# Dash_LEDs_r2.net
KiCad netlist of a schematic drawn in EAGLE
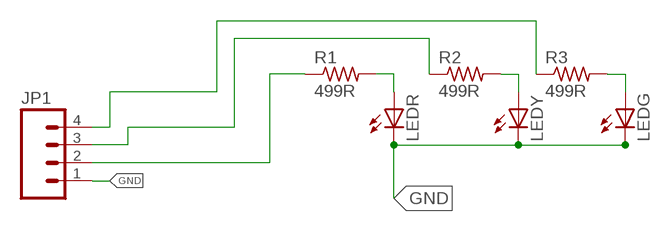
[diagram p0: schematic, sheet 1]

(export (version "E")
  (design (tool "Eeschema 10.0.6"))
  (components
    (comp (ref "JP1")
      (value "M04PTH")
      (footprint "eagle-import:1X04")
      (libsource (lib "eagle-import") (part "M04PTH"))
    )
    (comp (ref "LEDG")
      (value "LED5MM")
      (footprint "eagle-import:LED5MM")
      (libsource (lib "eagle-import") (part "LED5MM"))
    )
    (comp (ref "LEDR")
      (value "LED5MM")
      (footprint "eagle-import:LED5MM")
      (libsource (lib "eagle-import") (part "LED5MM"))
    )
    (comp (ref "LEDY")
      (value "LED5MM")
      (footprint "eagle-import:LED5MM")
      (libsource (lib "eagle-import") (part "LED5MM"))
    )
    (comp (ref "R1")
      (value "499R")
      (footprint "eagle-import:R0805")
      (libsource (lib "eagle-import") (part "R-US_R0805"))
    )
    (comp (ref "R2")
      (value "499R")
      (footprint "eagle-import:R0805")
      (libsource (lib "eagle-import") (part "R-US_R0805"))
    )
    (comp (ref "R3")
      (value "499R")
      (footprint "eagle-import:R0805")
      (libsource (lib "eagle-import") (part "R-US_R0805"))
    )
  )
  (nets
    (net (code "1") (name "GND") (class "Default")
      (node (ref "JP1") (pin "1") (pinfunction "1_1") (pintype "passive"))
      (node (ref "LEDG") (pin "K") (pinfunction "C_K") (pintype "passive"))
      (node (ref "LEDR") (pin "K") (pinfunction "C_K") (pintype "passive"))
      (node (ref "LEDY") (pin "K") (pinfunction "C_K") (pintype "passive"))
    )
    (net (code "2") (name "Net-(JP1-Pad2)") (class "Default")
      (node (ref "JP1") (pin "2") (pinfunction "2_2") (pintype "passive"))
      (node (ref "R1") (pin "1") (pinfunction "1_1") (pintype "passive"))
    )
    (net (code "3") (name "Net-(JP1-Pad3)") (class "Default")
      (node (ref "JP1") (pin "3") (pinfunction "3_3") (pintype "passive"))
      (node (ref "R2") (pin "1") (pinfunction "1_1") (pintype "passive"))
    )
    (net (code "4") (name "Net-(JP1-Pad4)") (class "Default")
      (node (ref "JP1") (pin "4") (pinfunction "4_4") (pintype "passive"))
      (node (ref "R3") (pin "1") (pinfunction "1_1") (pintype "passive"))
    )
    (net (code "5") (name "Net-(LEDG-PadA)") (class "Default")
      (node (ref "LEDG") (pin "A") (pinfunction "A_A") (pintype "passive"))
      (node (ref "R3") (pin "2") (pinfunction "2_2") (pintype "passive"))
    )
    (net (code "6") (name "Net-(LEDR-PadA)") (class "Default")
      (node (ref "LEDR") (pin "A") (pinfunction "A_A") (pintype "passive"))
      (node (ref "R1") (pin "2") (pinfunction "2_2") (pintype "passive"))
    )
    (net (code "7") (name "Net-(LEDY-PadA)") (class "Default")
      (node (ref "LEDY") (pin "A") (pinfunction "A_A") (pintype "passive"))
      (node (ref "R2") (pin "2") (pinfunction "2_2") (pintype "passive"))
    )
  )
)
